# Watch-It-TOP.net
KiCad netlist of a schematic drawn in EAGLE
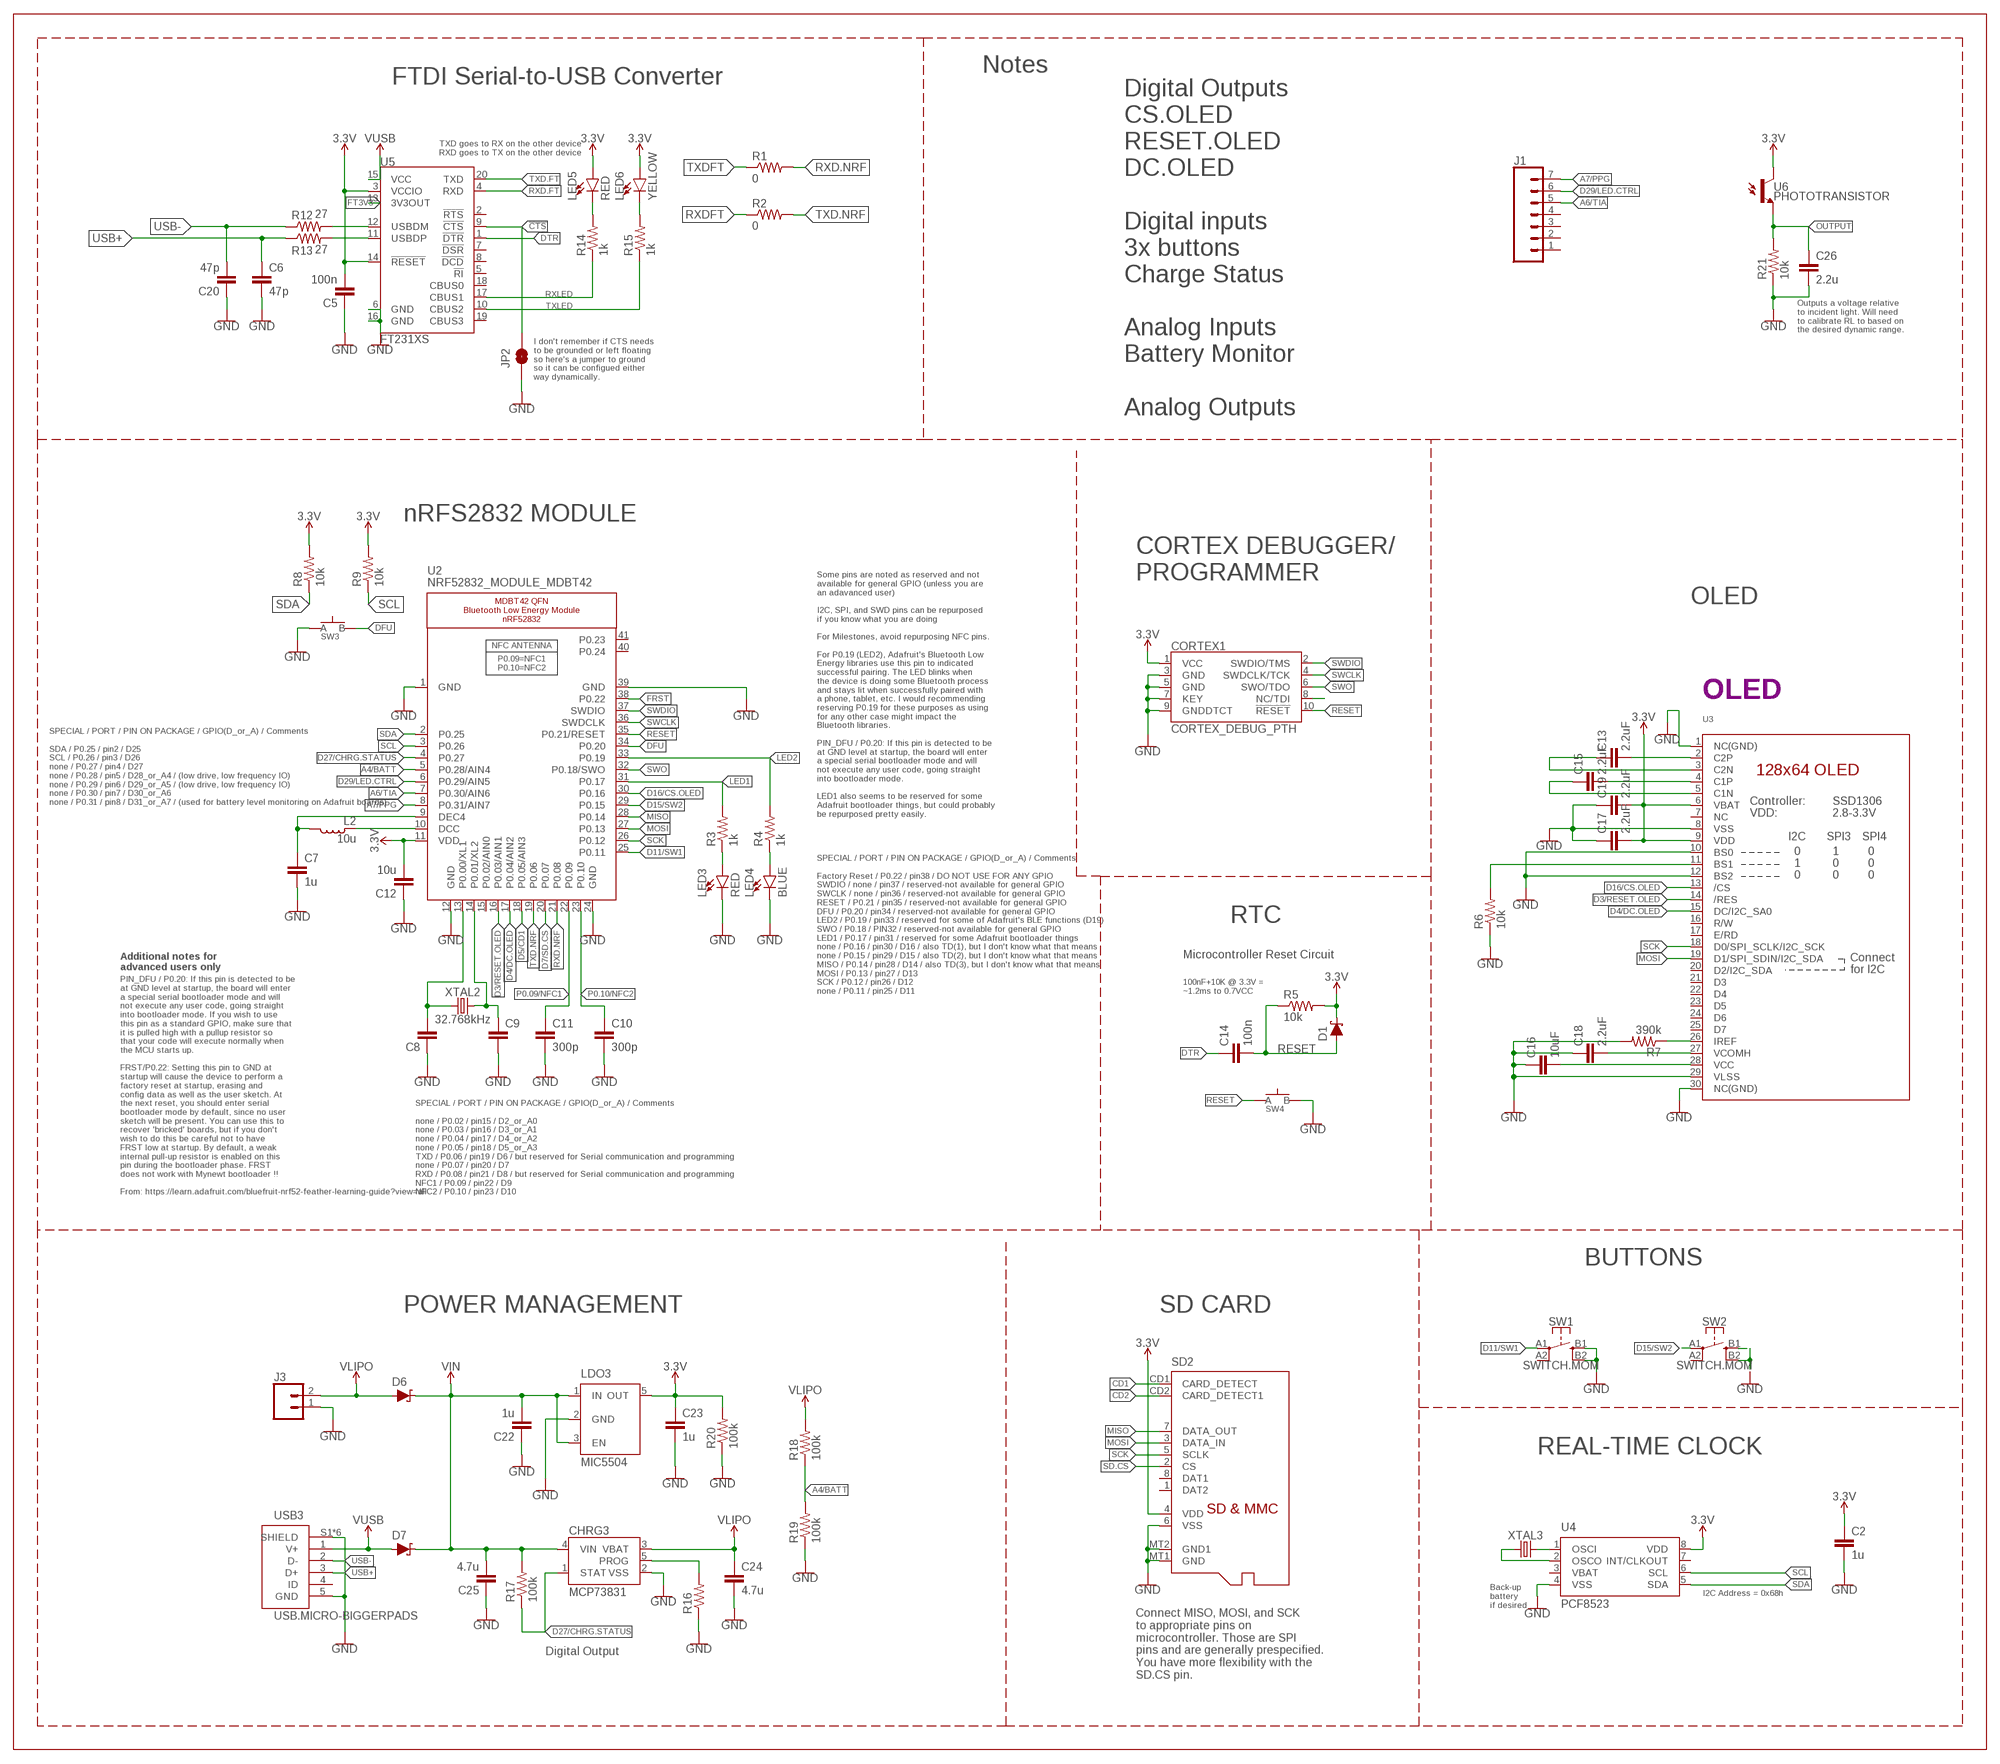
[diagram p0: schematic, sheet 1]

(export (version "E")
  (design (tool "Eeschema 10.0.6"))
  (components
    (comp (ref "C2")
      (value "1u")
      (footprint "eagle-import:C0603")
      (libsource (lib "eagle-import") (part "CAPACITOR0603"))
    )
    (comp (ref "C5")
      (value "100n")
      (footprint "eagle-import:C0603")
      (libsource (lib "eagle-import") (part "CAPACITOR0603"))
    )
    (comp (ref "C6")
      (value "47p")
      (footprint "eagle-import:C0603")
      (libsource (lib "eagle-import") (part "CAPACITOR0603"))
    )
    (comp (ref "C7")
      (value "1u")
      (footprint "eagle-import:C0603")
      (libsource (lib "eagle-import") (part "CAPACITOR0603"))
    )
    (comp (ref "C8")
      (value "CAPACITOR0603")
      (footprint "eagle-import:C0603")
      (libsource (lib "eagle-import") (part "CAPACITOR0603"))
    )
    (comp (ref "C9")
      (value "CAPACITOR0603")
      (footprint "eagle-import:C0603")
      (libsource (lib "eagle-import") (part "CAPACITOR0603"))
    )
    (comp (ref "C10")
      (value "300p")
      (footprint "eagle-import:C0603")
      (libsource (lib "eagle-import") (part "CAPACITOR0603"))
    )
    (comp (ref "C11")
      (value "300p")
      (footprint "eagle-import:C0603")
      (libsource (lib "eagle-import") (part "CAPACITOR0603"))
    )
    (comp (ref "C12")
      (value "10u")
      (footprint "eagle-import:C0805")
      (libsource (lib "eagle-import") (part "CAPACITOR0805"))
    )
    (comp (ref "C13")
      (value "2.2uF")
      (footprint "eagle-import:C0402")
      (libsource (lib "eagle-import") (part "CAPACITOR0402"))
    )
    (comp (ref "C14")
      (value "100n")
      (footprint "eagle-import:C0603")
      (libsource (lib "eagle-import") (part "CAPACITOR0603"))
    )
    (comp (ref "C15")
      (value "2.2uF")
      (footprint "eagle-import:C0402")
      (libsource (lib "eagle-import") (part "CAPACITOR0402"))
    )
    (comp (ref "C16")
      (value "10uF")
      (footprint "eagle-import:C0603")
      (libsource (lib "eagle-import") (part "CAPACITOR0603"))
    )
    (comp (ref "C17")
      (value "2.2uF")
      (footprint "eagle-import:C0402")
      (libsource (lib "eagle-import") (part "CAPACITOR0402"))
    )
    (comp (ref "C18")
      (value "2.2uF")
      (footprint "eagle-import:C0402")
      (libsource (lib "eagle-import") (part "CAPACITOR0402"))
    )
    (comp (ref "C19")
      (value "2.2uF")
      (footprint "eagle-import:C0402")
      (libsource (lib "eagle-import") (part "CAPACITOR0402"))
    )
    (comp (ref "C20")
      (value "47p")
      (footprint "eagle-import:C0603")
      (libsource (lib "eagle-import") (part "CAPACITOR0603"))
    )
    (comp (ref "C22")
      (value "1u")
      (footprint "eagle-import:C0603")
      (libsource (lib "eagle-import") (part "CAPACITOR0603"))
    )
    (comp (ref "C23")
      (value "1u")
      (footprint "eagle-import:C0603")
      (libsource (lib "eagle-import") (part "CAPACITOR0603"))
    )
    (comp (ref "C24")
      (value "4.7u")
      (footprint "eagle-import:C0603")
      (libsource (lib "eagle-import") (part "CAPACITOR0603"))
    )
    (comp (ref "C25")
      (value "4.7u")
      (footprint "eagle-import:C0603")
      (libsource (lib "eagle-import") (part "CAPACITOR0603"))
    )
    (comp (ref "C26")
      (value "2.2u")
      (footprint "eagle-import:C0603")
      (libsource (lib "eagle-import") (part "CAPACITOR0603"))
    )
    (comp (ref "CHRG3")
      (value "MCP73831")
      (footprint "eagle-import:SOT23-5")
      (libsource (lib "eagle-import") (part "MCP73831"))
    )
    (comp (ref "CORTEX1")
      (value "CORTEX_DEBUG_PTH")
      (footprint "eagle-import:2X5-PTH-1.27MM")
      (libsource (lib "eagle-import") (part "CORTEX_DEBUG_PTH"))
    )
    (comp (ref "D1")
      (value "SCHOTTKY-USC")
      (footprint "eagle-import:USC")
      (libsource (lib "eagle-import") (part "SCHOTTKY-USC"))
    )
    (comp (ref "D6")
      (value "SCHOTTKY-USC")
      (footprint "eagle-import:USC")
      (libsource (lib "eagle-import") (part "SCHOTTKY-USC"))
    )
    (comp (ref "D7")
      (value "SCHOTTKY-USC")
      (footprint "eagle-import:USC")
      (libsource (lib "eagle-import") (part "SCHOTTKY-USC"))
    )
    (comp (ref "J1")
      (value "CONN_07")
      (footprint "eagle-import:1X07")
      (libsource (lib "eagle-import") (part "CONN_07"))
    )
    (comp (ref "J3")
      (value "CONN_02")
      (footprint "eagle-import:1X02")
      (libsource (lib "eagle-import") (part "CONN_02"))
    )
    (comp (ref "JP2")
      (value "JUMPER-SMT_2_NO_SILK")
      (footprint "eagle-import:SMT-JUMPER_2_NO_SILK")
      (libsource (lib "eagle-import") (part "JUMPER-SMT_2_NO_SILK"))
    )
    (comp (ref "L2")
      (value "10u")
      (footprint "eagle-import:L0603")
      (libsource (lib "eagle-import") (part "INDUCTOR0603"))
    )
    (comp (ref "LDO3")
      (value "MIC5504")
      (footprint "eagle-import:SOT23-5")
      (libsource (lib "eagle-import") (part "MIC5504"))
    )
    (comp (ref "LED3")
      (value "RED")
      (footprint "eagle-import:LED-0603")
      (libsource (lib "eagle-import") (part "LED0603"))
    )
    (comp (ref "LED4")
      (value "BLUE")
      (footprint "eagle-import:LED-0603")
      (libsource (lib "eagle-import") (part "LED0603"))
    )
    (comp (ref "LED5")
      (value "RED")
      (footprint "eagle-import:LED-0603")
      (libsource (lib "eagle-import") (part "LED0603"))
    )
    (comp (ref "LED6")
      (value "YELLOW")
      (footprint "eagle-import:LED-0603")
      (libsource (lib "eagle-import") (part "LED0603"))
    )
    (comp (ref "R1")
      (value "0")
      (footprint "eagle-import:R0603")
      (libsource (lib "eagle-import") (part "RESISTOR0603"))
    )
    (comp (ref "R2")
      (value "0")
      (footprint "eagle-import:R0603")
      (libsource (lib "eagle-import") (part "RESISTOR0603"))
    )
    (comp (ref "R3")
      (value "1k")
      (footprint "eagle-import:R0603")
      (libsource (lib "eagle-import") (part "RESISTOR0603"))
    )
    (comp (ref "R4")
      (value "1k")
      (footprint "eagle-import:R0603")
      (libsource (lib "eagle-import") (part "RESISTOR0603"))
    )
    (comp (ref "R5")
      (value "10k")
      (footprint "eagle-import:R0603")
      (libsource (lib "eagle-import") (part "RESISTOR0603"))
    )
    (comp (ref "R6")
      (value "10k")
      (footprint "eagle-import:R0603")
      (libsource (lib "eagle-import") (part "RESISTOR0603"))
    )
    (comp (ref "R7")
      (value "390k")
      (footprint "eagle-import:R0603")
      (libsource (lib "eagle-import") (part "RESISTOR0603"))
    )
    (comp (ref "R8")
      (value "10k")
      (footprint "eagle-import:R0603")
      (libsource (lib "eagle-import") (part "RESISTOR0603"))
    )
    (comp (ref "R9")
      (value "10k")
      (footprint "eagle-import:R0603")
      (libsource (lib "eagle-import") (part "RESISTOR0603"))
    )
    (comp (ref "R12")
      (value "27")
      (footprint "eagle-import:R0603")
      (libsource (lib "eagle-import") (part "RESISTOR0603"))
    )
    (comp (ref "R13")
      (value "27")
      (footprint "eagle-import:R0603")
      (libsource (lib "eagle-import") (part "RESISTOR0603"))
    )
    (comp (ref "R14")
      (value "1k")
      (footprint "eagle-import:R0603")
      (libsource (lib "eagle-import") (part "RESISTOR0603"))
    )
    (comp (ref "R15")
      (value "1k")
      (footprint "eagle-import:R0603")
      (libsource (lib "eagle-import") (part "RESISTOR0603"))
    )
    (comp (ref "R16")
      (value "RESISTOR0603")
      (footprint "eagle-import:R0603")
      (libsource (lib "eagle-import") (part "RESISTOR0603"))
    )
    (comp (ref "R17")
      (value "100k")
      (footprint "eagle-import:R0603")
      (libsource (lib "eagle-import") (part "RESISTOR0603"))
    )
    (comp (ref "R18")
      (value "100k")
      (footprint "eagle-import:R0603")
      (libsource (lib "eagle-import") (part "RESISTOR0603"))
    )
    (comp (ref "R19")
      (value "100k")
      (footprint "eagle-import:R0603")
      (libsource (lib "eagle-import") (part "RESISTOR0603"))
    )
    (comp (ref "R20")
      (value "100k")
      (footprint "eagle-import:R0603")
      (libsource (lib "eagle-import") (part "RESISTOR0603"))
    )
    (comp (ref "R21")
      (value "10k")
      (footprint "eagle-import:R0603")
      (libsource (lib "eagle-import") (part "RESISTOR0603"))
    )
    (comp (ref "SD2")
      (value "MICROSD")
      (footprint "eagle-import:MICROSD")
      (libsource (lib "eagle-import") (part "MICROSD"))
    )
    (comp (ref "SW1")
      (value "SWITCH.MOM")
      (footprint "eagle-import:TACTILE_SWITCH_SMD_6.2MM_TALL")
      (libsource (lib "eagle-import") (part "SWITCH.MOM"))
    )
    (comp (ref "SW2")
      (value "SWITCH.MOM")
      (footprint "eagle-import:TACTILE_SWITCH_SMD_6.2MM_TALL")
      (libsource (lib "eagle-import") (part "SWITCH.MOM"))
    )
    (comp (ref "SW3")
      (value "SPST-PTS830GG140-COPY.1-3")
      (footprint "eagle-import:BUTTON-GULLWING")
      (libsource (lib "eagle-import") (part "SPST-PTS830GG140-COPY.1-3"))
    )
    (comp (ref "SW4")
      (value "SPST-PTS830GG140-COPY.1-3")
      (footprint "eagle-import:BUTTON-GULLWING")
      (libsource (lib "eagle-import") (part "SPST-PTS830GG140-COPY.1-3"))
    )
    (comp (ref "U2")
      (value "NRF52832_MODULE_MDBT42")
      (footprint "eagle-import:BLE_MODULE_RAYTAC_MDBT42")
      (libsource (lib "eagle-import") (part "NRF52832_MODULE_MDBT42"))
    )
    (comp (ref "U3")
      (value "DISP_OLED_UG-2864HSWEG01-NO-WRAPAROUND")
      (footprint "eagle-import:UG-2864HSWEG01_0.96IN_NO-WRAPAROUND")
      (libsource (lib "eagle-import") (part "DISP_OLED_UG-2864HSWEG01-NO-WRAPAROUND"))
    )
    (comp (ref "U4")
      (value "PCF8523")
      (footprint "eagle-import:SO8")
      (libsource (lib "eagle-import") (part "PCF8523"))
    )
    (comp (ref "U5")
      (value "FT231XS")
      (footprint "eagle-import:SSOP20_L")
      (libsource (lib "eagle-import") (part "FT231XS"))
    )
    (comp (ref "U6")
      (value "PHOTOTRANSISTOR")
      (footprint "eagle-import:R0603")
      (libsource (lib "eagle-import") (part "PHOTOTRANSISTOR"))
    )
    (comp (ref "USB3")
      (value "USB.MICRO-BIGGERPADS")
      (footprint "eagle-import:USB-MICRO-01.BIGGERPADS")
      (libsource (lib "eagle-import") (part "USB.MICRO-BIGGERPADS"))
    )
    (comp (ref "XTAL2")
      (value "32.768kHz")
      (footprint "eagle-import:2-SMD.NOLEAD.2.0MMTO1.2MM")
      (libsource (lib "eagle-import") (part "CRYSTALECS-.327-12.5-12-C-TR"))
    )
    (comp (ref "XTAL3")
      (value "32.7680kHz")
      (footprint "eagle-import:2-SMD.NOLEAD.2.0MMTO1.2MM")
      (libsource (lib "eagle-import") (part "CRYSTALECS-.327-12.5-12-C-TR"))
    )
  )
  (nets
    (net (code "1") (name "/RXLED") (class "Default")
      (node (ref "R14") (pin "1") (pinfunction "1_1") (pintype "passive"))
      (node (ref "U5") (pin "17") (pinfunction "CBUS1_17") (pintype "bidirectional"))
    )
    (net (code "2") (name "/TXLED") (class "Default")
      (node (ref "R15") (pin "1") (pinfunction "1_1") (pintype "passive"))
      (node (ref "U5") (pin "10") (pinfunction "CBUS2_10") (pintype "bidirectional"))
    )
    (net (code "3") (name "/VBAT") (class "Default")
      (node (ref "U4") (pin "3") (pinfunction "VBAT_3") (pintype "power_in"))
    )
    (net (code "4") (name "/~{CTS}") (class "Default")
      (node (ref "JP2") (pin "2") (pinfunction "2_2") (pintype "passive"))
      (node (ref "U5") (pin "9") (pinfunction "~{CTS}_9") (pintype "bidirectional"))
    )
    (net (code "5") (name "3.3V") (class "Default")
      (node (ref "C12") (pin "2") (pinfunction "2_2") (pintype "passive"))
      (node (ref "C17") (pin "2") (pinfunction "2_2") (pintype "passive"))
      (node (ref "C19") (pin "2") (pinfunction "2_2") (pintype "passive"))
      (node (ref "C2") (pin "1") (pinfunction "1_1") (pintype "passive"))
      (node (ref "C23") (pin "1") (pinfunction "1_1") (pintype "passive"))
      (node (ref "C5") (pin "2") (pinfunction "2_2") (pintype "passive"))
      (node (ref "CORTEX1") (pin "1") (pinfunction "VCC_1") (pintype "bidirectional"))
      (node (ref "D1") (pin "-") (pinfunction "C_-") (pintype "passive"))
      (node (ref "LDO3") (pin "5") (pinfunction "OUT_5") (pintype "bidirectional"))
      (node (ref "LED5") (pin "A") (pinfunction "A_A") (pintype "passive"))
      (node (ref "LED6") (pin "A") (pinfunction "A_A") (pintype "passive"))
      (node (ref "R20") (pin "2") (pinfunction "2_2") (pintype "passive"))
      (node (ref "R5") (pin "2") (pinfunction "2_2") (pintype "passive"))
      (node (ref "R8") (pin "2") (pinfunction "2_2") (pintype "passive"))
      (node (ref "R9") (pin "2") (pinfunction "2_2") (pintype "passive"))
      (node (ref "SD2") (pin "4") (pinfunction "VDD_4") (pintype "power_in"))
      (node (ref "U2") (pin "11") (pinfunction "VDD_11") (pintype "bidirectional"))
      (node (ref "U3") (pin "6") (pinfunction "VBAT_6") (pintype "input"))
      (node (ref "U3") (pin "9") (pinfunction "VDD_9") (pintype "power_in"))
      (node (ref "U4") (pin "8") (pinfunction "VDD_8") (pintype "power_in"))
      (node (ref "U5") (pin "14") (pinfunction "~{RESET}_14") (pintype "bidirectional"))
      (node (ref "U5") (pin "3") (pinfunction "VCCIO_3") (pintype "bidirectional"))
      (node (ref "U6") (pin "1") (pinfunction "C_1") (pintype "passive"))
    )
    (net (code "6") (name "A4{slash}BATT") (class "Default")
      (node (ref "R18") (pin "1") (pinfunction "1_1") (pintype "passive"))
      (node (ref "R19") (pin "2") (pinfunction "2_2") (pintype "passive"))
      (node (ref "U2") (pin "5") (pinfunction "P0.28/AIN4_5") (pintype "bidirectional"))
    )
    (net (code "7") (name "A6{slash}TIA") (class "Default")
      (node (ref "J1") (pin "5") (pinfunction "5_5") (pintype "passive"))
      (node (ref "U2") (pin "7") (pinfunction "P0.30/AIN6_7") (pintype "bidirectional"))
    )
    (net (code "8") (name "A7{slash}PPG") (class "Default")
      (node (ref "J1") (pin "7") (pinfunction "7_7") (pintype "passive"))
      (node (ref "U2") (pin "8") (pinfunction "P0.31/AIN7_8") (pintype "bidirectional"))
    )
    (net (code "9") (name "CD1") (class "Default")
      (node (ref "SD2") (pin "CD1") (pinfunction "CARD_DETECT_CD1") (pintype "passive"))
    )
    (net (code "10") (name "CD2") (class "Default")
      (node (ref "SD2") (pin "CD2") (pinfunction "CARD_DETECT1_CD2") (pintype "passive"))
    )
    (net (code "11") (name "D3{slash}RESET.OLED") (class "Default")
      (node (ref "U2") (pin "16") (pinfunction "P0.03/AIN1_16") (pintype "bidirectional"))
      (node (ref "U3") (pin "14") (pinfunction "/RES_14") (pintype "input"))
    )
    (net (code "12") (name "D4{slash}DC.OLED") (class "Default")
      (node (ref "U2") (pin "17") (pinfunction "P0.04/AIN2_17") (pintype "bidirectional"))
      (node (ref "U3") (pin "15") (pinfunction "DC/I2C_SA0_15") (pintype "input"))
    )
    (net (code "13") (name "D5{slash}CD1") (class "Default")
      (node (ref "U2") (pin "18") (pinfunction "P0.05/AIN3_18") (pintype "bidirectional"))
    )
    (net (code "14") (name "D7{slash}SD.CS") (class "Default")
      (node (ref "U2") (pin "20") (pinfunction "P0.07_20") (pintype "bidirectional"))
    )
    (net (code "15") (name "D11{slash}SW1") (class "Default")
      (node (ref "SW1") (pin "A1") (pinfunction "1_A1") (pintype "passive"))
      (node (ref "U2") (pin "25") (pinfunction "P0.11_25") (pintype "bidirectional"))
    )
    (net (code "16") (name "D15{slash}SW2") (class "Default")
      (node (ref "SW2") (pin "A1") (pinfunction "1_A1") (pintype "passive"))
      (node (ref "U2") (pin "29") (pinfunction "P0.15_29") (pintype "bidirectional"))
    )
    (net (code "17") (name "D16{slash}CS.OLED") (class "Default")
      (node (ref "U2") (pin "30") (pinfunction "P0.16_30") (pintype "bidirectional"))
      (node (ref "U3") (pin "13") (pinfunction "/CS_13") (pintype "input"))
    )
    (net (code "18") (name "D27{slash}CHRG.STATUS") (class "Default")
      (node (ref "CHRG3") (pin "1") (pinfunction "STAT_1") (pintype "output"))
      (node (ref "R17") (pin "1") (pinfunction "1_1") (pintype "passive"))
      (node (ref "U2") (pin "4") (pinfunction "P0.27_4") (pintype "bidirectional"))
    )
    (net (code "19") (name "D29{slash}LED.CTRL") (class "Default")
      (node (ref "J1") (pin "6") (pinfunction "6_6") (pintype "passive"))
      (node (ref "U2") (pin "6") (pinfunction "P0.29/AIN5_6") (pintype "bidirectional"))
    )
    (net (code "20") (name "DFU") (class "Default")
      (node (ref "SW3") (pin "3") (pinfunction "B_3") (pintype "bidirectional"))
      (node (ref "U2") (pin "34") (pinfunction "P0.20_34") (pintype "bidirectional"))
    )
    (net (code "21") (name "DTR") (class "Default")
      (node (ref "C14") (pin "1") (pinfunction "1_1") (pintype "passive"))
      (node (ref "U5") (pin "1") (pinfunction "~{DTR}_1") (pintype "bidirectional"))
    )
    (net (code "22") (name "FRST") (class "Default")
      (node (ref "U2") (pin "38") (pinfunction "P0.22_38") (pintype "bidirectional"))
    )
    (net (code "23") (name "FT3V3") (class "Default")
      (node (ref "U5") (pin "13") (pinfunction "3V3OUT_13") (pintype "bidirectional"))
    )
    (net (code "24") (name "GND") (class "Default")
      (node (ref "C10") (pin "2") (pinfunction "2_2") (pintype "passive"))
      (node (ref "C11") (pin "2") (pinfunction "2_2") (pintype "passive"))
      (node (ref "C12") (pin "1") (pinfunction "1_1") (pintype "passive"))
      (node (ref "C16") (pin "1") (pinfunction "1_1") (pintype "passive"))
      (node (ref "C17") (pin "1") (pinfunction "1_1") (pintype "passive"))
      (node (ref "C18") (pin "1") (pinfunction "1_1") (pintype "passive"))
      (node (ref "C19") (pin "1") (pinfunction "1_1") (pintype "passive"))
      (node (ref "C2") (pin "2") (pinfunction "2_2") (pintype "passive"))
      (node (ref "C20") (pin "1") (pinfunction "1_1") (pintype "passive"))
      (node (ref "C22") (pin "1") (pinfunction "1_1") (pintype "passive"))
      (node (ref "C23") (pin "2") (pinfunction "2_2") (pintype "passive"))
      (node (ref "C24") (pin "2") (pinfunction "2_2") (pintype "passive"))
      (node (ref "C25") (pin "1") (pinfunction "1_1") (pintype "passive"))
      (node (ref "C26") (pin "2") (pinfunction "2_2") (pintype "passive"))
      (node (ref "C5") (pin "1") (pinfunction "1_1") (pintype "passive"))
      (node (ref "C6") (pin "2") (pinfunction "2_2") (pintype "passive"))
      (node (ref "C7") (pin "2") (pinfunction "2_2") (pintype "passive"))
      (node (ref "C8") (pin "1") (pinfunction "1_1") (pintype "passive"))
      (node (ref "C9") (pin "2") (pinfunction "2_2") (pintype "passive"))
      (node (ref "CHRG3") (pin "2") (pinfunction "VSS_2") (pintype "power_in"))
      (node (ref "CORTEX1") (pin "3") (pinfunction "GND_3") (pintype "bidirectional"))
      (node (ref "CORTEX1") (pin "5") (pinfunction "GND_5") (pintype "bidirectional"))
      (node (ref "CORTEX1") (pin "7") (pinfunction "KEY_7") (pintype "bidirectional"))
      (node (ref "CORTEX1") (pin "9") (pinfunction "GNDDTCT_9") (pintype "bidirectional"))
      (node (ref "J3") (pin "1") (pinfunction "1_1") (pintype "passive"))
      (node (ref "JP2") (pin "1") (pinfunction "1_1") (pintype "passive"))
      (node (ref "LDO3") (pin "2") (pinfunction "GND_2") (pintype "bidirectional"))
      (node (ref "LED3") (pin "C") (pinfunction "C_C") (pintype "passive"))
      (node (ref "LED4") (pin "C") (pinfunction "C_C") (pintype "passive"))
      (node (ref "R16") (pin "1") (pinfunction "1_1") (pintype "passive"))
      (node (ref "R19") (pin "1") (pinfunction "1_1") (pintype "passive"))
      (node (ref "R20") (pin "1") (pinfunction "1_1") (pintype "passive"))
      (node (ref "R21") (pin "1") (pinfunction "1_1") (pintype "passive"))
      (node (ref "R6") (pin "1") (pinfunction "1_1") (pintype "passive"))
      (node (ref "R7") (pin "2") (pinfunction "2_2") (pintype "passive"))
      (node (ref "SD2") (pin "6") (pinfunction "VSS_6") (pintype "power_in"))
      (node (ref "SD2") (pin "MT1") (pinfunction "GND_MT1") (pintype "power_in"))
      (node (ref "SD2") (pin "MT2") (pinfunction "GND1_MT2") (pintype "power_in"))
      (node (ref "SW1") (pin "B1") (pinfunction "3_B1") (pintype "passive"))
      (node (ref "SW1") (pin "B2") (pinfunction "4_B2") (pintype "passive"))
      (node (ref "SW2") (pin "B1") (pinfunction "3_B1") (pintype "passive"))
      (node (ref "SW2") (pin "B2") (pinfunction "4_B2") (pintype "passive"))
      (node (ref "SW3") (pin "1") (pinfunction "A_1") (pintype "bidirectional"))
      (node (ref "SW4") (pin "3") (pinfunction "B_3") (pintype "bidirectional"))
      (node (ref "U2") (pin "1") (pinfunction "GND_1") (pintype "bidirectional"))
      (node (ref "U2") (pin "12") (pinfunction "GND_12") (pintype "bidirectional"))
      (node (ref "U2") (pin "24") (pinfunction "GND_24") (pintype "bidirectional"))
      (node (ref "U2") (pin "39") (pinfunction "GND_39") (pintype "bidirectional"))
      (node (ref "U3") (pin "1") (pinfunction "NC(GND)_1") (pintype "input"))
      (node (ref "U3") (pin "10") (pinfunction "BS0_10") (pintype "input"))
      (node (ref "U3") (pin "12") (pinfunction "BS2_12") (pintype "input"))
      (node (ref "U3") (pin "29") (pinfunction "VLSS_29") (pintype "power_in"))
      (node (ref "U3") (pin "30") (pinfunction "NC(GND)_30") (pintype "input"))
      (node (ref "U3") (pin "8") (pinfunction "VSS_8") (pintype "power_in"))
      (node (ref "U4") (pin "4") (pinfunction "VSS_4") (pintype "power_in"))
      (node (ref "U5") (pin "16") (pinfunction "GND_16") (pintype "bidirectional"))
      (node (ref "U5") (pin "6") (pinfunction "GND_6") (pintype "bidirectional"))
      (node (ref "USB3") (pin "5") (pinfunction "GND_5") (pintype "bidirectional"))
      (node (ref "USB3") (pin "S1") (pinfunction "SHIELD_S1") (pintype "bidirectional"))
      (node (ref "USB3") (pin "S2") (pinfunction "SHIELD_S2") (pintype "bidirectional"))
      (node (ref "USB3") (pin "S3") (pinfunction "SHIELD_S3") (pintype "bidirectional"))
      (node (ref "USB3") (pin "S4") (pinfunction "SHIELD_S4") (pintype "bidirectional"))
      (node (ref "USB3") (pin "S5") (pinfunction "SHIELD_S5") (pintype "bidirectional"))
      (node (ref "USB3") (pin "S6") (pinfunction "SHIELD_S6") (pintype "bidirectional"))
    )
    (net (code "25") (name "LED1") (class "Default")
      (node (ref "R3") (pin "2") (pinfunction "2_2") (pintype "passive"))
      (node (ref "U2") (pin "31") (pinfunction "P0.17_31") (pintype "bidirectional"))
    )
    (net (code "26") (name "LED2") (class "Default")
      (node (ref "R4") (pin "2") (pinfunction "2_2") (pintype "passive"))
      (node (ref "U2") (pin "33") (pinfunction "P0.19_33") (pintype "bidirectional"))
    )
    (net (code "27") (name "MISO") (class "Default")
      (node (ref "SD2") (pin "7") (pinfunction "DATA_OUT_7") (pintype "output"))
      (node (ref "U2") (pin "28") (pinfunction "P0.14_28") (pintype "bidirectional"))
    )
    (net (code "28") (name "MOSI") (class "Default")
      (node (ref "SD2") (pin "3") (pinfunction "DATA_IN_3") (pintype "input"))
      (node (ref "U2") (pin "27") (pinfunction "P0.13_27") (pintype "bidirectional"))
      (node (ref "U3") (pin "19") (pinfunction "D1/SPI_SDIN/I2C_SDA_19") (pintype "bidirectional"))
    )
    (net (code "29") (name "Net-(CHRG3-PROG)") (class "Default")
      (node (ref "CHRG3") (pin "5") (pinfunction "PROG_5") (pintype "input"))
      (node (ref "R16") (pin "2") (pinfunction "2_2") (pintype "passive"))
    )
    (net (code "30") (name "Net-(LED3-PadA)") (class "Default")
      (node (ref "LED3") (pin "A") (pinfunction "A_A") (pintype "passive"))
      (node (ref "R3") (pin "1") (pinfunction "1_1") (pintype "passive"))
    )
    (net (code "31") (name "Net-(LED4-PadA)") (class "Default")
      (node (ref "LED4") (pin "A") (pinfunction "A_A") (pintype "passive"))
      (node (ref "R4") (pin "1") (pinfunction "1_1") (pintype "passive"))
    )
    (net (code "32") (name "Net-(LED5-PadC)") (class "Default")
      (node (ref "LED5") (pin "C") (pinfunction "C_C") (pintype "passive"))
      (node (ref "R14") (pin "2") (pinfunction "2_2") (pintype "passive"))
    )
    (net (code "33") (name "Net-(LED6-PadC)") (class "Default")
      (node (ref "LED6") (pin "C") (pinfunction "C_C") (pintype "passive"))
      (node (ref "R15") (pin "2") (pinfunction "2_2") (pintype "passive"))
    )
    (net (code "34") (name "Net-(U2-DCC)") (class "Default")
      (node (ref "L2") (pin "1") (pinfunction "1_1") (pintype "passive"))
      (node (ref "U2") (pin "10") (pinfunction "DCC_10") (pintype "bidirectional"))
    )
    (net (code "35") (name "Net-(U2-DEC4)") (class "Default")
      (node (ref "C7") (pin "1") (pinfunction "1_1") (pintype "passive"))
      (node (ref "L2") (pin "2") (pinfunction "2_2") (pintype "passive"))
      (node (ref "U2") (pin "9") (pinfunction "DEC4_9") (pintype "bidirectional"))
    )
    (net (code "36") (name "Net-(U2-P0.00{slash}XL1)") (class "Default")
      (node (ref "C8") (pin "2") (pinfunction "2_2") (pintype "passive"))
      (node (ref "U2") (pin "13") (pinfunction "P0.00/XL1_13") (pintype "bidirectional"))
      (node (ref "XTAL2") (pin "P$1") (pinfunction "1_P$1") (pintype "passive"))
    )
    (net (code "37") (name "Net-(U2-P0.01{slash}XL2)") (class "Default")
      (node (ref "C9") (pin "1") (pinfunction "1_1") (pintype "passive"))
      (node (ref "U2") (pin "14") (pinfunction "P0.01/XL2_14") (pintype "bidirectional"))
      (node (ref "XTAL2") (pin "P$2") (pinfunction "2_P$2") (pintype "passive"))
    )
    (net (code "38") (name "Net-(U3-BS1)") (class "Default")
      (node (ref "R6") (pin "2") (pinfunction "2_2") (pintype "passive"))
      (node (ref "U3") (pin "11") (pinfunction "BS1_11") (pintype "input"))
    )
    (net (code "39") (name "Net-(U3-C1N)") (class "Default")
      (node (ref "C15") (pin "1") (pinfunction "1_1") (pintype "passive"))
      (node (ref "U3") (pin "5") (pinfunction "C1N_5") (pintype "input"))
    )
    (net (code "40") (name "Net-(U3-C1P)") (class "Default")
      (node (ref "C15") (pin "2") (pinfunction "2_2") (pintype "passive"))
      (node (ref "U3") (pin "4") (pinfunction "C1P_4") (pintype "input"))
    )
    (net (code "41") (name "Net-(U3-C2N)") (class "Default")
      (node (ref "C13") (pin "1") (pinfunction "1_1") (pintype "passive"))
      (node (ref "U3") (pin "3") (pinfunction "C2N_3") (pintype "input"))
    )
    (net (code "42") (name "Net-(U3-C2P)") (class "Default")
      (node (ref "C13") (pin "2") (pinfunction "2_2") (pintype "passive"))
      (node (ref "U3") (pin "2") (pinfunction "C2P_2") (pintype "input"))
    )
    (net (code "43") (name "Net-(U3-IREF)") (class "Default")
      (node (ref "R7") (pin "1") (pinfunction "1_1") (pintype "passive"))
      (node (ref "U3") (pin "26") (pinfunction "IREF_26") (pintype "input"))
    )
    (net (code "44") (name "Net-(U3-VCC)") (class "Default")
      (node (ref "C16") (pin "2") (pinfunction "2_2") (pintype "passive"))
      (node (ref "U3") (pin "28") (pinfunction "VCC_28") (pintype "power_in"))
    )
    (net (code "45") (name "Net-(U3-VCOMH)") (class "Default")
      (node (ref "C18") (pin "2") (pinfunction "2_2") (pintype "passive"))
      (node (ref "U3") (pin "27") (pinfunction "VCOMH_27") (pintype "output"))
    )
    (net (code "46") (name "Net-(U4-OSCI)") (class "Default")
      (node (ref "U4") (pin "1") (pinfunction "OSCI_1") (pintype "bidirectional"))
      (node (ref "XTAL3") (pin "P$2") (pinfunction "2_P$2") (pintype "passive"))
    )
    (net (code "47") (name "Net-(U4-OSCO)") (class "Default")
      (node (ref "U4") (pin "2") (pinfunction "OSCO_2") (pintype "bidirectional"))
      (node (ref "XTAL3") (pin "P$1") (pinfunction "1_P$1") (pintype "passive"))
    )
    (net (code "48") (name "Net-(U5-USBDM)") (class "Default")
      (node (ref "R12") (pin "2") (pinfunction "2_2") (pintype "passive"))
      (node (ref "U5") (pin "12") (pinfunction "USBDM_12") (pintype "bidirectional"))
    )
    (net (code "49") (name "Net-(U5-USBDP)") (class "Default")
      (node (ref "R13") (pin "2") (pinfunction "2_2") (pintype "passive"))
      (node (ref "U5") (pin "11") (pinfunction "USBDP_11") (pintype "bidirectional"))
    )
    (net (code "50") (name "OUTPUT") (class "Default")
      (node (ref "C26") (pin "1") (pinfunction "1_1") (pintype "passive"))
      (node (ref "R21") (pin "2") (pinfunction "2_2") (pintype "passive"))
      (node (ref "U6") (pin "2") (pinfunction "E_2") (pintype "passive"))
    )
    (net (code "51") (name "P0.09{slash}NFC1") (class "Default")
      (node (ref "C11") (pin "1") (pinfunction "1_1") (pintype "passive"))
      (node (ref "U2") (pin "22") (pinfunction "P0.09_22") (pintype "bidirectional"))
    )
    (net (code "52") (name "P0.10{slash}NFC2") (class "Default")
      (node (ref "C10") (pin "1") (pinfunction "1_1") (pintype "passive"))
      (node (ref "U2") (pin "23") (pinfunction "P0.10_23") (pintype "bidirectional"))
    )
    (net (code "53") (name "RESET") (class "Default")
      (node (ref "C14") (pin "2") (pinfunction "2_2") (pintype "passive"))
      (node (ref "CORTEX1") (pin "10") (pinfunction "~{RESET}_10") (pintype "bidirectional"))
      (node (ref "D1") (pin "+") (pinfunction "A_+") (pintype "passive"))
      (node (ref "R5") (pin "1") (pinfunction "1_1") (pintype "passive"))
      (node (ref "SW4") (pin "1") (pinfunction "A_1") (pintype "bidirectional"))
      (node (ref "U2") (pin "35") (pinfunction "P0.21/RESET_35") (pintype "bidirectional"))
    )
    (net (code "54") (name "RXD.FT") (class "Default")
      (node (ref "U5") (pin "4") (pinfunction "RXD_4") (pintype "bidirectional"))
    )
    (net (code "55") (name "RXD.NRF") (class "Default")
      (node (ref "R1") (pin "2") (pinfunction "2_2") (pintype "passive"))
      (node (ref "U2") (pin "21") (pinfunction "P0.08_21") (pintype "bidirectional"))
    )
    (net (code "56") (name "RXDFT") (class "Default")
      (node (ref "R2") (pin "1") (pinfunction "1_1") (pintype "passive"))
    )
    (net (code "57") (name "SCK") (class "Default")
      (node (ref "SD2") (pin "5") (pinfunction "SCLK_5") (pintype "input"))
      (node (ref "U2") (pin "26") (pinfunction "P0.12_26") (pintype "bidirectional"))
      (node (ref "U3") (pin "18") (pinfunction "D0/SPI_SCLK/I2C_SCK_18") (pintype "bidirectional"))
    )
    (net (code "58") (name "SCL") (class "Default")
      (node (ref "R9") (pin "1") (pinfunction "1_1") (pintype "passive"))
      (node (ref "U2") (pin "3") (pinfunction "P0.26_3") (pintype "bidirectional"))
      (node (ref "U4") (pin "6") (pinfunction "SCL_6") (pintype "bidirectional"))
    )
    (net (code "59") (name "SD.CS") (class "Default")
      (node (ref "SD2") (pin "2") (pinfunction "CS_2") (pintype "input"))
    )
    (net (code "60") (name "SDA") (class "Default")
      (node (ref "R8") (pin "1") (pinfunction "1_1") (pintype "passive"))
      (node (ref "U2") (pin "2") (pinfunction "P0.25_2") (pintype "bidirectional"))
      (node (ref "U4") (pin "5") (pinfunction "SDA_5") (pintype "bidirectional"))
    )
    (net (code "61") (name "SWCLK") (class "Default")
      (node (ref "CORTEX1") (pin "4") (pinfunction "SWDCLK/TCK_4") (pintype "bidirectional"))
      (node (ref "U2") (pin "36") (pinfunction "SWDCLK_36") (pintype "bidirectional"))
    )
    (net (code "62") (name "SWDIO") (class "Default")
      (node (ref "CORTEX1") (pin "2") (pinfunction "SWDIO/TMS_2") (pintype "bidirectional"))
      (node (ref "U2") (pin "37") (pinfunction "SWDIO_37") (pintype "bidirectional"))
    )
    (net (code "63") (name "SWO") (class "Default")
      (node (ref "CORTEX1") (pin "6") (pinfunction "SWO/TDO_6") (pintype "bidirectional"))
      (node (ref "U2") (pin "32") (pinfunction "P0.18/SWO_32") (pintype "bidirectional"))
    )
    (net (code "64") (name "TXD.FT") (class "Default")
      (node (ref "U5") (pin "20") (pinfunction "TXD_20") (pintype "bidirectional"))
    )
    (net (code "65") (name "TXD.NRF") (class "Default")
      (node (ref "R2") (pin "2") (pinfunction "2_2") (pintype "passive"))
      (node (ref "U2") (pin "19") (pinfunction "P0.06_19") (pintype "bidirectional"))
    )
    (net (code "66") (name "TXDFT") (class "Default")
      (node (ref "R1") (pin "1") (pinfunction "1_1") (pintype "passive"))
    )
    (net (code "67") (name "USB+") (class "Default")
      (node (ref "C6") (pin "1") (pinfunction "1_1") (pintype "passive"))
      (node (ref "R13") (pin "1") (pinfunction "1_1") (pintype "passive"))
      (node (ref "USB3") (pin "3") (pinfunction "D+_3") (pintype "bidirectional"))
    )
    (net (code "68") (name "USB-") (class "Default")
      (node (ref "C20") (pin "2") (pinfunction "2_2") (pintype "passive"))
      (node (ref "R12") (pin "1") (pinfunction "1_1") (pintype "passive"))
      (node (ref "USB3") (pin "2") (pinfunction "D-_2") (pintype "bidirectional"))
    )
    (net (code "69") (name "VIN") (class "Default")
      (node (ref "C22") (pin "2") (pinfunction "2_2") (pintype "passive"))
      (node (ref "C25") (pin "2") (pinfunction "2_2") (pintype "passive"))
      (node (ref "CHRG3") (pin "4") (pinfunction "VIN_4") (pintype "power_in"))
      (node (ref "D6") (pin "-") (pinfunction "C_-") (pintype "passive"))
      (node (ref "D7") (pin "-") (pinfunction "C_-") (pintype "passive"))
      (node (ref "LDO3") (pin "1") (pinfunction "IN_1") (pintype "bidirectional"))
      (node (ref "LDO3") (pin "3") (pinfunction "EN_3") (pintype "bidirectional"))
      (node (ref "R17") (pin "2") (pinfunction "2_2") (pintype "passive"))
    )
    (net (code "70") (name "VLIPO") (class "Default")
      (node (ref "C24") (pin "1") (pinfunction "1_1") (pintype "passive"))
      (node (ref "CHRG3") (pin "3") (pinfunction "VBAT_3") (pintype "power_in"))
      (node (ref "D6") (pin "+") (pinfunction "A_+") (pintype "passive"))
      (node (ref "J3") (pin "2") (pinfunction "2_2") (pintype "passive"))
      (node (ref "R18") (pin "2") (pinfunction "2_2") (pintype "passive"))
    )
    (net (code "71") (name "VUSB") (class "Default")
      (node (ref "D7") (pin "+") (pinfunction "A_+") (pintype "passive"))
      (node (ref "U5") (pin "15") (pinfunction "VCC_15") (pintype "bidirectional"))
      (node (ref "USB3") (pin "1") (pinfunction "V+_1") (pintype "bidirectional"))
    )
    (net (code "72") (name "unconnected-(CORTEX1-NC{slash}TDI-Pad8)") (class "Default")
      (node (ref "CORTEX1") (pin "8") (pinfunction "NC/TDI_8") (pintype "bidirectional"))
    )
    (net (code "73") (name "unconnected-(J1-Pad1)") (class "Default")
      (node (ref "J1") (pin "1") (pinfunction "1_1") (pintype "passive"))
    )
    (net (code "74") (name "unconnected-(J1-Pad2)") (class "Default")
      (node (ref "J1") (pin "2") (pinfunction "2_2") (pintype "passive"))
    )
    (net (code "75") (name "unconnected-(J1-Pad3)") (class "Default")
      (node (ref "J1") (pin "3") (pinfunction "3_3") (pintype "passive"))
    )
    (net (code "76") (name "unconnected-(J1-Pad4)") (class "Default")
      (node (ref "J1") (pin "4") (pinfunction "4_4") (pintype "passive"))
    )
    (net (code "77") (name "unconnected-(SD2-DAT1-Pad8)") (class "Default")
      (node (ref "SD2") (pin "8") (pinfunction "DAT1_8") (pintype "bidirectional"))
    )
    (net (code "78") (name "unconnected-(SD2-DAT2-Pad1)") (class "Default")
      (node (ref "SD2") (pin "1") (pinfunction "DAT2_1") (pintype "bidirectional"))
    )
    (net (code "79") (name "unconnected-(SW1-2-PadA2)") (class "Default")
      (node (ref "SW1") (pin "A2") (pinfunction "2_A2") (pintype "passive"))
    )
    (net (code "80") (name "unconnected-(SW2-2-PadA2)") (class "Default")
      (node (ref "SW2") (pin "A2") (pinfunction "2_A2") (pintype "passive"))
    )
    (net (code "81") (name "unconnected-(U2-P0.02{slash}AIN0-Pad15)") (class "Default")
      (node (ref "U2") (pin "15") (pinfunction "P0.02/AIN0_15") (pintype "bidirectional"))
    )
    (net (code "82") (name "unconnected-(U2-P0.23-Pad41)") (class "Default")
      (node (ref "U2") (pin "41") (pinfunction "P0.23_41") (pintype "bidirectional"))
    )
    (net (code "83") (name "unconnected-(U2-P0.24-Pad40)") (class "Default")
      (node (ref "U2") (pin "40") (pinfunction "P0.24_40") (pintype "bidirectional"))
    )
    (net (code "84") (name "unconnected-(U3-D2{slash}I2C_SDA-Pad20)") (class "Default")
      (node (ref "U3") (pin "20") (pinfunction "D2/I2C_SDA_20") (pintype "bidirectional"))
    )
    (net (code "85") (name "unconnected-(U3-D3-Pad21)") (class "Default")
      (node (ref "U3") (pin "21") (pinfunction "D3_21") (pintype "bidirectional"))
    )
    (net (code "86") (name "unconnected-(U3-D4-Pad22)") (class "Default")
      (node (ref "U3") (pin "22") (pinfunction "D4_22") (pintype "bidirectional"))
    )
    (net (code "87") (name "unconnected-(U3-D5-Pad23)") (class "Default")
      (node (ref "U3") (pin "23") (pinfunction "D5_23") (pintype "bidirectional"))
    )
    (net (code "88") (name "unconnected-(U3-D6-Pad24)") (class "Default")
      (node (ref "U3") (pin "24") (pinfunction "D6_24") (pintype "bidirectional"))
    )
    (net (code "89") (name "unconnected-(U3-D7-Pad25)") (class "Default")
      (node (ref "U3") (pin "25") (pinfunction "D7_25") (pintype "bidirectional"))
    )
    (net (code "90") (name "unconnected-(U3-E{slash}RD-Pad17)") (class "Default")
      (node (ref "U3") (pin "17") (pinfunction "E/RD_17") (pintype "input"))
    )
    (net (code "91") (name "unconnected-(U3-NC-Pad7)") (class "Default")
      (node (ref "U3") (pin "7") (pinfunction "NC_7") (pintype "no_connect"))
    )
    (net (code "92") (name "unconnected-(U3-R{slash}W-Pad16)") (class "Default")
      (node (ref "U3") (pin "16") (pinfunction "R/W_16") (pintype "input"))
    )
    (net (code "93") (name "unconnected-(U4-INT{slash}CLKOUT-Pad7)") (class "Default")
      (node (ref "U4") (pin "7") (pinfunction "INT/CLKOUT_7") (pintype "bidirectional"))
    )
    (net (code "94") (name "unconnected-(U5-CBUS0-Pad18)") (class "Default")
      (node (ref "U5") (pin "18") (pinfunction "CBUS0_18") (pintype "bidirectional"))
    )
    (net (code "95") (name "unconnected-(U5-CBUS3-Pad19)") (class "Default")
      (node (ref "U5") (pin "19") (pinfunction "CBUS3_19") (pintype "bidirectional"))
    )
    (net (code "96") (name "unconnected-(U5-~{DCD}-Pad8)") (class "Default")
      (node (ref "U5") (pin "8") (pinfunction "~{DCD}_8") (pintype "bidirectional"))
    )
    (net (code "97") (name "unconnected-(U5-~{DSR}-Pad7)") (class "Default")
      (node (ref "U5") (pin "7") (pinfunction "~{DSR}_7") (pintype "bidirectional"))
    )
    (net (code "98") (name "unconnected-(U5-~{RI}-Pad5)") (class "Default")
      (node (ref "U5") (pin "5") (pinfunction "~{RI}_5") (pintype "bidirectional"))
    )
    (net (code "99") (name "unconnected-(U5-~{RTS}-Pad2)") (class "Default")
      (node (ref "U5") (pin "2") (pinfunction "~{RTS}_2") (pintype "bidirectional"))
    )
    (net (code "100") (name "unconnected-(USB3-ID-Pad4)") (class "Default")
      (node (ref "USB3") (pin "4") (pinfunction "ID_4") (pintype "bidirectional"))
    )
  )
)
